# mt3608.net
KiCad netlist of a schematic drawn in Altium Designer
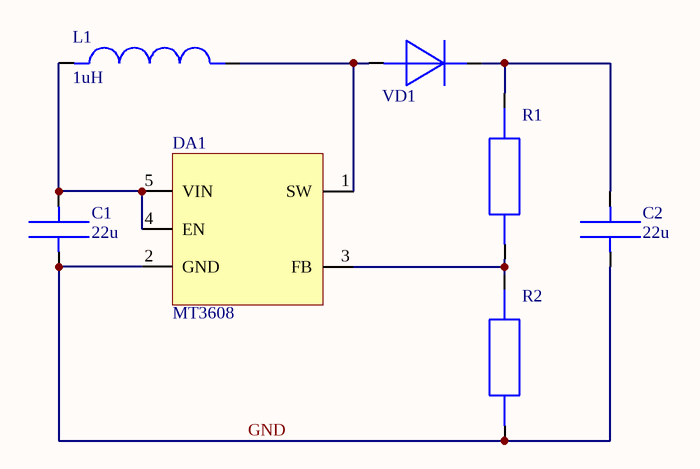
[diagram p0: mt3608.SchDoc]

(export (version "E")
  (design (tool "Eeschema 10.0.6"))
  (components
    (comp (ref "C1") (value "22u") (footprint "C1206") (libsource (lib "mt3608_Schlib1") (part "C1210")))
    (comp (ref "C2") (value "22u") (footprint "C1206") (libsource (lib "mt3608_Schlib1") (part "C1210")))
    (comp (ref "DA1")
      (value "MT3608")
      (footprint "SOT23-6")
      (libsource (lib "mt3608_Schlib1") (part "MT3608"))
    )
    (comp (ref "L1")
      (value "1uH")
      (footprint "L_CDRH104R")
      (libsource (lib "mt3608_Schlib1") (part "L_CDRH104R"))
    )
    (comp (ref "R1") (value "~") (footprint "R0805") (libsource (lib "mt3608_Schlib1") (part "R0805")))
    (comp (ref "R2") (value "~") (footprint "R0805") (libsource (lib "mt3608_Schlib1") (part "R0805")))
    (comp (ref "VD1") (value "VD_SMB") (footprint "SMB") (libsource (lib "mt3608_Schlib1") (part "VD_SMB")))
  )
  (nets
    (net (code "1") (name "/GND") (class "Default")
      (node (ref "C1") (pin "1") (pinfunction "1_1") (pintype "passive"))
      (node (ref "C2") (pin "1") (pinfunction "1_1") (pintype "passive"))
      (node (ref "DA1") (pin "2") (pinfunction "GND_2") (pintype "passive"))
      (node (ref "R2") (pin "1") (pinfunction "1_1") (pintype "passive"))
    )
    (net (code "2") (name "Net-(C2-Pad2)") (class "Default")
      (node (ref "C2") (pin "2") (pinfunction "2_2") (pintype "passive"))
      (node (ref "R1") (pin "2") (pinfunction "2_2") (pintype "passive"))
      (node (ref "VD1") (pin "2") (pinfunction "2_2") (pintype "passive"))
    )
    (net (code "3") (name "Net-(DA1-EN)") (class "Default")
      (node (ref "C1") (pin "2") (pinfunction "2_2") (pintype "passive"))
      (node (ref "DA1") (pin "4") (pinfunction "EN_4") (pintype "passive"))
      (node (ref "DA1") (pin "5") (pinfunction "VIN_5") (pintype "passive"))
      (node (ref "L1") (pin "1") (pinfunction "1_1") (pintype "passive"))
    )
    (net (code "4") (name "Net-(DA1-FB)") (class "Default")
      (node (ref "DA1") (pin "3") (pinfunction "FB_3") (pintype "passive"))
      (node (ref "R1") (pin "1") (pinfunction "1_1") (pintype "passive"))
      (node (ref "R2") (pin "2") (pinfunction "2_2") (pintype "passive"))
    )
    (net (code "5") (name "Net-(DA1-SW)") (class "Default")
      (node (ref "DA1") (pin "1") (pinfunction "SW_1") (pintype "passive"))
      (node (ref "L1") (pin "2") (pinfunction "2_2") (pintype "passive"))
      (node (ref "VD1") (pin "1") (pinfunction "1_1") (pintype "passive"))
    )
  )
)
